# Filter_V0_2.net
KiCad netlist of a schematic drawn in EAGLE
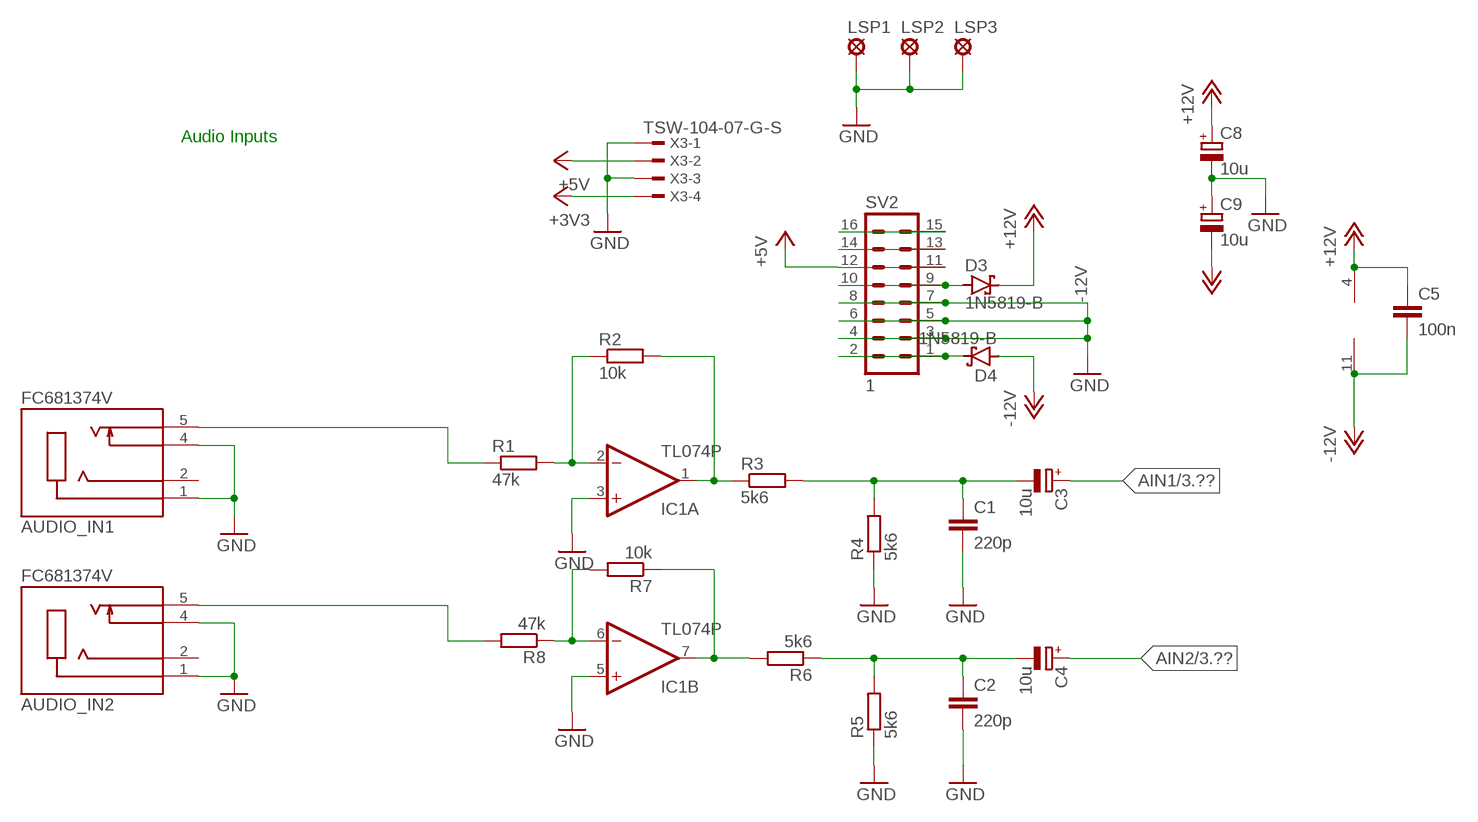
[diagram p0: schematic, sheet 1]
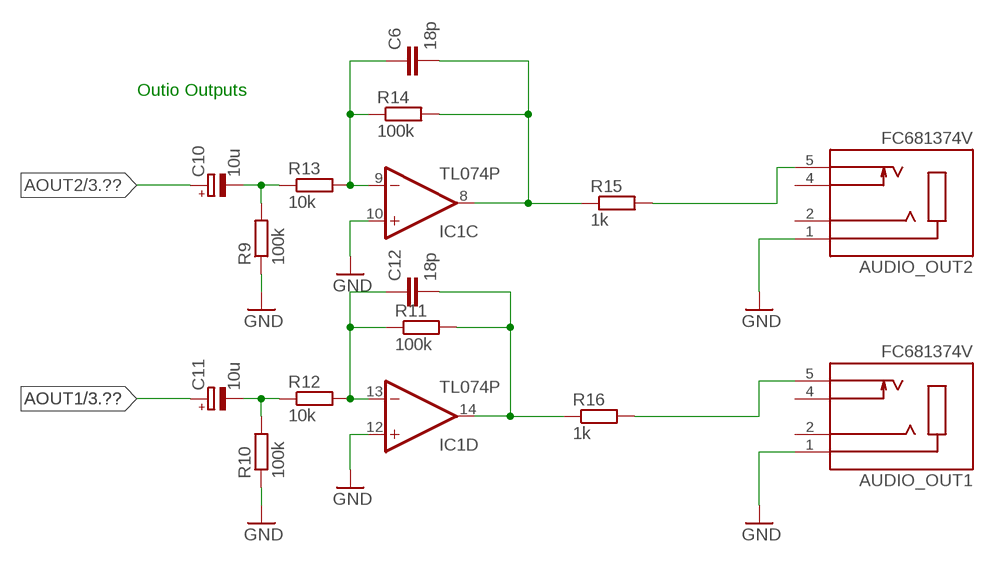
[diagram p1: schematic, sheet 2]
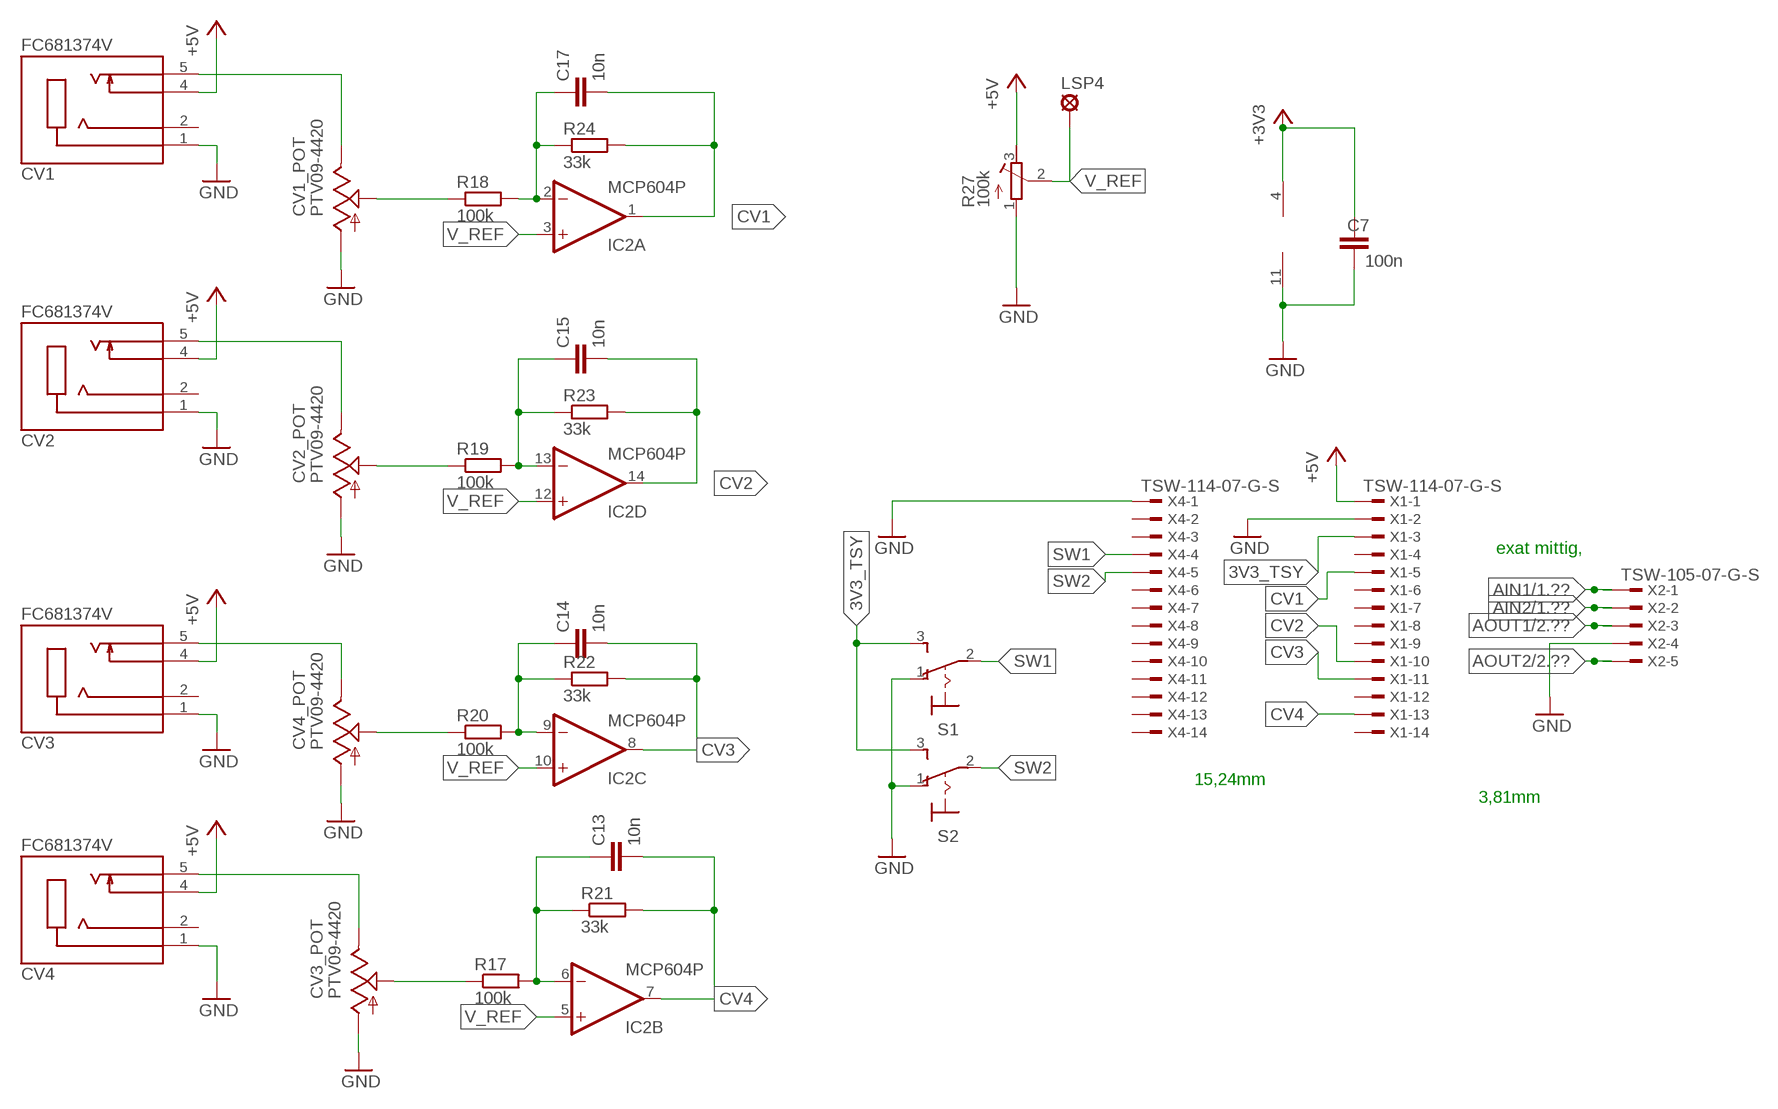
[diagram p2: schematic, sheet 3]

(export (version "E")
  (design (tool "Eeschema 10.0.6"))
  (components
    (comp (ref "C7")
      (value "100n")
      (footprint "eagle-import:C025-024X044")
      (libsource (lib "eagle-import") (part "C-EU025-024X044"))
    )
    (comp (ref "C13")
      (value "10n")
      (footprint "eagle-import:C025-024X044")
      (libsource (lib "eagle-import") (part "C-EU025-024X044"))
    )
    (comp (ref "C14")
      (value "10n")
      (footprint "eagle-import:C025-024X044")
      (libsource (lib "eagle-import") (part "C-EU025-024X044"))
    )
    (comp (ref "C15")
      (value "10n")
      (footprint "eagle-import:C025-024X044")
      (libsource (lib "eagle-import") (part "C-EU025-024X044"))
    )
    (comp (ref "C17")
      (value "10n")
      (footprint "eagle-import:C025-024X044")
      (libsource (lib "eagle-import") (part "C-EU025-024X044"))
    )
    (comp (ref "CV1")
      (value "FC681374V")
      (footprint "eagle-import:CLIFF_FC681374V")
      (fields (field (name "MF") "Cliff"))
      (libsource (lib "eagle-import") (part "FC681374V"))
    )
    (comp (ref "CV1_POT")
      (value "PTV09-4420")
      (footprint "eagle-import:PTV09")
      (fields (field (name "MF") "Nichifu") (field (name "MP") "PTV-09"))
      (libsource (lib "eagle-import") (part "PTV09-4420"))
    )
    (comp (ref "CV2")
      (value "FC681374V")
      (footprint "eagle-import:CLIFF_FC681374V")
      (fields (field (name "MF") "Cliff"))
      (libsource (lib "eagle-import") (part "FC681374V"))
    )
    (comp (ref "CV2_POT")
      (value "PTV09-4420")
      (footprint "eagle-import:PTV09")
      (fields (field (name "MF") "Nichifu") (field (name "MP") "PTV-09"))
      (libsource (lib "eagle-import") (part "PTV09-4420"))
    )
    (comp (ref "CV3")
      (value "FC681374V")
      (footprint "eagle-import:CLIFF_FC681374V")
      (fields (field (name "MF") "Cliff"))
      (libsource (lib "eagle-import") (part "FC681374V"))
    )
    (comp (ref "CV3_POT")
      (value "PTV09-4420")
      (footprint "eagle-import:PTV09")
      (fields (field (name "MF") "Nichifu") (field (name "MP") "PTV-09"))
      (libsource (lib "eagle-import") (part "PTV09-4420"))
    )
    (comp (ref "CV4")
      (value "FC681374V")
      (footprint "eagle-import:CLIFF_FC681374V")
      (fields (field (name "MF") "Cliff"))
      (libsource (lib "eagle-import") (part "FC681374V"))
    )
    (comp (ref "CV4_POT")
      (value "PTV09-4420")
      (footprint "eagle-import:PTV09")
      (fields (field (name "MF") "Nichifu") (field (name "MP") "PTV-09"))
      (libsource (lib "eagle-import") (part "PTV09-4420"))
    )
    (comp (ref "IC2")
      (value "MCP604P")
      (footprint "eagle-import:DIL14")
      (fields (field (name "SPICEPREFIX") "J"))
      (libsource (lib "eagle-import") (part "MCP604P"))
    )
    (comp (ref "LSP4")
      (value "LSP10")
      (footprint "eagle-import:LSP10")
      (libsource (lib "eagle-import") (part "LSP10"))
    )
    (comp (ref "R17")
      (value "100k")
      (footprint "eagle-import:0204_7")
      (libsource (lib "eagle-import") (part "R-EU_0204/7"))
    )
    (comp (ref "R18")
      (value "100k")
      (footprint "eagle-import:0204_7")
      (libsource (lib "eagle-import") (part "R-EU_0204/7"))
    )
    (comp (ref "R19")
      (value "100k")
      (footprint "eagle-import:0204_7")
      (libsource (lib "eagle-import") (part "R-EU_0204/7"))
    )
    (comp (ref "R20")
      (value "100k")
      (footprint "eagle-import:0204_7")
      (libsource (lib "eagle-import") (part "R-EU_0204/7"))
    )
    (comp (ref "R21")
      (value "33k")
      (footprint "eagle-import:0204_7")
      (libsource (lib "eagle-import") (part "R-EU_0204/7"))
    )
    (comp (ref "R22")
      (value "33k")
      (footprint "eagle-import:0204_7")
      (libsource (lib "eagle-import") (part "R-EU_0204/7"))
    )
    (comp (ref "R23")
      (value "33k")
      (footprint "eagle-import:0204_7")
      (libsource (lib "eagle-import") (part "R-EU_0204/7"))
    )
    (comp (ref "R24")
      (value "33k")
      (footprint "eagle-import:0204_7")
      (libsource (lib "eagle-import") (part "R-EU_0204/7"))
    )
    (comp (ref "R27")
      (value "100k")
      (footprint "eagle-import:RTRIM64W")
      (libsource (lib "eagle-import") (part "R-TRIMM64W"))
    )
    (comp (ref "S1")
      (value "M9040P")
      (footprint "eagle-import:M9040P")
      (libsource (lib "eagle-import") (part "M9040P"))
    )
    (comp (ref "S2")
      (value "M9040P")
      (footprint "eagle-import:M9040P")
      (libsource (lib "eagle-import") (part "M9040P"))
    )
    (comp (ref "X1")
      (value "TSW-114-07-G-S")
      (footprint "eagle-import:TSW-114-XX-G-S")
      (fields (field (name "MF") "Samtec Inc."))
      (libsource (lib "eagle-import") (part "TSW-114--G-S07"))
    )
    (comp (ref "X2")
      (value "TSW-105-07-G-S")
      (footprint "eagle-import:TSW-105-XX-G-S")
      (fields (field (name "MF") "Samtec Inc."))
      (libsource (lib "eagle-import") (part "TSW-105--G-S07"))
    )
    (comp (ref "X4")
      (value "TSW-114-07-G-S")
      (footprint "eagle-import:TSW-114-XX-G-S")
      (fields (field (name "MF") "Samtec Inc."))
      (libsource (lib "eagle-import") (part "TSW-114--G-S07"))
    )
    (comp (ref "AUDIO_IN1")
      (value "FC681374V")
      (footprint "eagle-import:CLIFF_FC681374V")
      (fields (field (name "MF") "Cliff"))
      (libsource (lib "eagle-import") (part "FC681374V"))
    )
    (comp (ref "AUDIO_IN2")
      (value "FC681374V")
      (footprint "eagle-import:CLIFF_FC681374V")
      (fields (field (name "MF") "Cliff"))
      (libsource (lib "eagle-import") (part "FC681374V"))
    )
    (comp (ref "C1")
      (value "220p")
      (footprint "eagle-import:C025-024X044")
      (libsource (lib "eagle-import") (part "C-EU025-024X044"))
    )
    (comp (ref "C2")
      (value "220p")
      (footprint "eagle-import:C025-024X044")
      (libsource (lib "eagle-import") (part "C-EU025-024X044"))
    )
    (comp (ref "C3")
      (value "10u")
      (footprint "eagle-import:E2,5-7")
      (libsource (lib "eagle-import") (part "CPOL-EUE2.5-7"))
    )
    (comp (ref "C4")
      (value "10u")
      (footprint "eagle-import:E2,5-7")
      (libsource (lib "eagle-import") (part "CPOL-EUE2.5-7"))
    )
    (comp (ref "C5")
      (value "100n")
      (footprint "eagle-import:C025-024X044")
      (libsource (lib "eagle-import") (part "C-EU025-024X044"))
    )
    (comp (ref "C8")
      (value "10u")
      (footprint "eagle-import:E2,5-7")
      (libsource (lib "eagle-import") (part "CPOL-EUE2.5-7"))
    )
    (comp (ref "C9")
      (value "10u")
      (footprint "eagle-import:E2,5-7")
      (libsource (lib "eagle-import") (part "CPOL-EUE2.5-7"))
    )
    (comp (ref "D3")
      (value "1N5819-B")
      (footprint "eagle-import:DO41-7.6")
      (libsource (lib "eagle-import") (part "1N5819-B"))
    )
    (comp (ref "D4")
      (value "1N5819-B")
      (footprint "eagle-import:DO41-7.6")
      (libsource (lib "eagle-import") (part "1N5819-B"))
    )
    (comp (ref "IC1")
      (value "TL074P")
      (footprint "eagle-import:DIL14")
      (libsource (lib "eagle-import") (part "TL074P"))
    )
    (comp (ref "LSP1")
      (value "LSP10")
      (footprint "eagle-import:LSP10")
      (libsource (lib "eagle-import") (part "LSP10"))
    )
    (comp (ref "LSP2")
      (value "LSP10")
      (footprint "eagle-import:LSP10")
      (libsource (lib "eagle-import") (part "LSP10"))
    )
    (comp (ref "LSP3")
      (value "LSP10")
      (footprint "eagle-import:LSP10")
      (libsource (lib "eagle-import") (part "LSP10"))
    )
    (comp (ref "R1")
      (value "47k")
      (footprint "eagle-import:0204_7")
      (libsource (lib "eagle-import") (part "R-EU_0204/7"))
    )
    (comp (ref "R2")
      (value "10k")
      (footprint "eagle-import:0204_7")
      (libsource (lib "eagle-import") (part "R-EU_0204/7"))
    )
    (comp (ref "R3")
      (value "5k6")
      (footprint "eagle-import:0204_7")
      (libsource (lib "eagle-import") (part "R-EU_0204/7"))
    )
    (comp (ref "R4")
      (value "5k6")
      (footprint "eagle-import:0204_7")
      (libsource (lib "eagle-import") (part "R-EU_0204/7"))
    )
    (comp (ref "R5")
      (value "5k6")
      (footprint "eagle-import:0204_7")
      (libsource (lib "eagle-import") (part "R-EU_0204/7"))
    )
    (comp (ref "R6")
      (value "5k6")
      (footprint "eagle-import:0204_7")
      (libsource (lib "eagle-import") (part "R-EU_0204/7"))
    )
    (comp (ref "R7")
      (value "10k")
      (footprint "eagle-import:0204_7")
      (libsource (lib "eagle-import") (part "R-EU_0204/7"))
    )
    (comp (ref "R8")
      (value "47k")
      (footprint "eagle-import:0204_7")
      (libsource (lib "eagle-import") (part "R-EU_0204/7"))
    )
    (comp (ref "SV2")
      (value "1")
      (footprint "eagle-import:ML16")
      (libsource (lib "eagle-import") (part "ML16"))
    )
    (comp (ref "X3")
      (value "TSW-104-07-G-S")
      (footprint "eagle-import:TSW-104-XX-G-S")
      (fields (field (name "MF") "Samtec Inc."))
      (libsource (lib "eagle-import") (part "TSW-104--G-S07"))
    )
    (comp (ref "AUDIO_OUT1")
      (value "FC681374V")
      (footprint "eagle-import:CLIFF_FC681374V")
      (fields (field (name "MF") "Cliff"))
      (libsource (lib "eagle-import") (part "FC681374V"))
    )
    (comp (ref "AUDIO_OUT2")
      (value "FC681374V")
      (footprint "eagle-import:CLIFF_FC681374V")
      (fields (field (name "MF") "Cliff"))
      (libsource (lib "eagle-import") (part "FC681374V"))
    )
    (comp (ref "C6")
      (value "18p")
      (footprint "eagle-import:C025-024X044")
      (libsource (lib "eagle-import") (part "C-EU025-024X044"))
    )
    (comp (ref "C10")
      (value "10u")
      (footprint "eagle-import:E2,5-7")
      (libsource (lib "eagle-import") (part "CPOL-EUE2.5-7"))
    )
    (comp (ref "C11")
      (value "10u")
      (footprint "eagle-import:E2,5-7")
      (libsource (lib "eagle-import") (part "CPOL-EUE2.5-7"))
    )
    (comp (ref "C12")
      (value "18p")
      (footprint "eagle-import:C025-024X044")
      (libsource (lib "eagle-import") (part "C-EU025-024X044"))
    )
    (comp (ref "R9")
      (value "100k")
      (footprint "eagle-import:0204_7")
      (libsource (lib "eagle-import") (part "R-EU_0204/7"))
    )
    (comp (ref "R10")
      (value "100k")
      (footprint "eagle-import:0204_7")
      (libsource (lib "eagle-import") (part "R-EU_0204/7"))
    )
    (comp (ref "R11")
      (value "100k")
      (footprint "eagle-import:0204_7")
      (libsource (lib "eagle-import") (part "R-EU_0204/7"))
    )
    (comp (ref "R12")
      (value "10k")
      (footprint "eagle-import:0204_7")
      (libsource (lib "eagle-import") (part "R-EU_0204/7"))
    )
    (comp (ref "R13")
      (value "10k")
      (footprint "eagle-import:0204_7")
      (libsource (lib "eagle-import") (part "R-EU_0204/7"))
    )
    (comp (ref "R14")
      (value "100k")
      (footprint "eagle-import:0204_7")
      (libsource (lib "eagle-import") (part "R-EU_0204/7"))
    )
    (comp (ref "R15")
      (value "1k")
      (footprint "eagle-import:0204_7")
      (libsource (lib "eagle-import") (part "R-EU_0204/7"))
    )
    (comp (ref "R16")
      (value "1k")
      (footprint "eagle-import:0204_7")
      (libsource (lib "eagle-import") (part "R-EU_0204/7"))
    )
  )
  (nets
    (net (code "1") (name "+3V3") (class "Default")
      (node (ref "C7") (pin "1") (pinfunction "1_1") (pintype "passive"))
      (node (ref "IC2") (pin "4") (pinfunction "V+_4") (pintype "power_in"))
      (node (ref "X3") (pin "4") (pinfunction "1_4") (pintype "passive"))
    )
    (net (code "2") (name "+5V") (class "Default")
      (node (ref "CV1") (pin "4") (pinfunction "4_4") (pintype "passive"))
      (node (ref "CV2") (pin "4") (pinfunction "4_4") (pintype "passive"))
      (node (ref "CV3") (pin "4") (pinfunction "4_4") (pintype "passive"))
      (node (ref "CV4") (pin "4") (pinfunction "4_4") (pintype "passive"))
      (node (ref "R27") (pin "3") (pinfunction "E_3") (pintype "passive"))
      (node (ref "SV2") (pin "11") (pinfunction "11_11") (pintype "passive"))
      (node (ref "SV2") (pin "12") (pinfunction "12_12") (pintype "passive"))
      (node (ref "X1") (pin "1") (pinfunction "1_1") (pintype "passive"))
      (node (ref "X3") (pin "2") (pinfunction "1_2") (pintype "passive"))
    )
    (net (code "3") (name "+12V") (class "Default")
      (node (ref "C5") (pin "1") (pinfunction "1_1") (pintype "passive"))
      (node (ref "C8") (pin "+") (pinfunction "+_+") (pintype "passive"))
      (node (ref "D3") (pin "C") (pinfunction "C_C") (pintype "passive"))
      (node (ref "IC1") (pin "4") (pinfunction "V+_4") (pintype "power_in"))
    )
    (net (code "4") (name "-12V") (class "Default")
      (node (ref "C5") (pin "2") (pinfunction "2_2") (pintype "passive"))
      (node (ref "C9") (pin "-") (pinfunction "-_-") (pintype "passive"))
      (node (ref "D4") (pin "A") (pinfunction "A_A") (pintype "passive"))
      (node (ref "IC1") (pin "11") (pinfunction "V-_11") (pintype "power_in"))
    )
    (net (code "5") (name "3V3_TSY") (class "Default")
      (node (ref "S1") (pin "3") (pinfunction "S_3") (pintype "passive"))
      (node (ref "S2") (pin "3") (pinfunction "S_3") (pintype "passive"))
      (node (ref "X1") (pin "3") (pinfunction "1_3") (pintype "passive"))
    )
    (net (code "6") (name "AIN1") (class "Default")
      (node (ref "C3") (pin "+") (pinfunction "+_+") (pintype "passive"))
      (node (ref "X2") (pin "1") (pinfunction "1_1") (pintype "passive"))
    )
    (net (code "7") (name "AIN2") (class "Default")
      (node (ref "C4") (pin "+") (pinfunction "+_+") (pintype "passive"))
      (node (ref "X2") (pin "2") (pinfunction "1_2") (pintype "passive"))
    )
    (net (code "8") (name "AOUT1") (class "Default")
      (node (ref "C11") (pin "+") (pinfunction "+_+") (pintype "passive"))
      (node (ref "X2") (pin "3") (pinfunction "1_3") (pintype "passive"))
    )
    (net (code "9") (name "AOUT2") (class "Default")
      (node (ref "C10") (pin "+") (pinfunction "+_+") (pintype "passive"))
      (node (ref "X2") (pin "5") (pinfunction "1_5") (pintype "passive"))
    )
    (net (code "10") (name "CV1") (class "Default")
      (node (ref "C17") (pin "2") (pinfunction "2_2") (pintype "passive"))
      (node (ref "IC2") (pin "1") (pinfunction "OUT_1") (pintype "output"))
      (node (ref "R24") (pin "2") (pinfunction "2_2") (pintype "passive"))
      (node (ref "X1") (pin "5") (pinfunction "1_5") (pintype "passive"))
    )
    (net (code "11") (name "CV2") (class "Default")
      (node (ref "C15") (pin "2") (pinfunction "2_2") (pintype "passive"))
      (node (ref "IC2") (pin "14") (pinfunction "OUT_14") (pintype "output"))
      (node (ref "R23") (pin "2") (pinfunction "2_2") (pintype "passive"))
      (node (ref "X1") (pin "10") (pinfunction "1_10") (pintype "passive"))
    )
    (net (code "12") (name "CV3") (class "Default")
      (node (ref "C14") (pin "2") (pinfunction "2_2") (pintype "passive"))
      (node (ref "IC2") (pin "8") (pinfunction "OUT_8") (pintype "output"))
      (node (ref "R22") (pin "2") (pinfunction "2_2") (pintype "passive"))
      (node (ref "X1") (pin "11") (pinfunction "1_11") (pintype "passive"))
    )
    (net (code "13") (name "CV4") (class "Default")
      (node (ref "C13") (pin "2") (pinfunction "2_2") (pintype "passive"))
      (node (ref "IC2") (pin "7") (pinfunction "OUT_7") (pintype "output"))
      (node (ref "R21") (pin "2") (pinfunction "2_2") (pintype "passive"))
      (node (ref "X1") (pin "13") (pinfunction "1_13") (pintype "passive"))
    )
    (net (code "14") (name "GND") (class "Default")
      (node (ref "AUDIO_IN1") (pin "1") (pinfunction "1_1") (pintype "passive"))
      (node (ref "AUDIO_IN1") (pin "4") (pinfunction "4_4") (pintype "passive"))
      (node (ref "AUDIO_IN2") (pin "1") (pinfunction "1_1") (pintype "passive"))
      (node (ref "AUDIO_IN2") (pin "4") (pinfunction "4_4") (pintype "passive"))
      (node (ref "AUDIO_OUT1") (pin "1") (pinfunction "1_1") (pintype "passive"))
      (node (ref "AUDIO_OUT2") (pin "1") (pinfunction "1_1") (pintype "passive"))
      (node (ref "C1") (pin "2") (pinfunction "2_2") (pintype "passive"))
      (node (ref "C2") (pin "2") (pinfunction "2_2") (pintype "passive"))
      (node (ref "C7") (pin "2") (pinfunction "2_2") (pintype "passive"))
      (node (ref "C8") (pin "-") (pinfunction "-_-") (pintype "passive"))
      (node (ref "C9") (pin "+") (pinfunction "+_+") (pintype "passive"))
      (node (ref "CV1") (pin "1") (pinfunction "1_1") (pintype "passive"))
      (node (ref "CV1_POT") (pin "1") (pinfunction "A_1") (pintype "passive"))
      (node (ref "CV2") (pin "1") (pinfunction "1_1") (pintype "passive"))
      (node (ref "CV2_POT") (pin "1") (pinfunction "A_1") (pintype "passive"))
      (node (ref "CV3") (pin "1") (pinfunction "1_1") (pintype "passive"))
      (node (ref "CV3_POT") (pin "1") (pinfunction "A_1") (pintype "passive"))
      (node (ref "CV4") (pin "1") (pinfunction "1_1") (pintype "passive"))
      (node (ref "CV4_POT") (pin "1") (pinfunction "A_1") (pintype "passive"))
      (node (ref "IC1") (pin "10") (pinfunction "+IN_10") (pintype "input"))
      (node (ref "IC1") (pin "12") (pinfunction "+IN_12") (pintype "input"))
      (node (ref "IC1") (pin "3") (pinfunction "+IN_3") (pintype "input"))
      (node (ref "IC1") (pin "5") (pinfunction "+IN_5") (pintype "input"))
      (node (ref "IC2") (pin "11") (pinfunction "V-_11") (pintype "power_in"))
      (node (ref "LSP1") (pin "MP") (pinfunction "MP_MP") (pintype "passive"))
      (node (ref "LSP2") (pin "MP") (pinfunction "MP_MP") (pintype "passive"))
      (node (ref "LSP3") (pin "MP") (pinfunction "MP_MP") (pintype "passive"))
      (node (ref "R10") (pin "1") (pinfunction "1_1") (pintype "passive"))
      (node (ref "R27") (pin "1") (pinfunction "A_1") (pintype "passive"))
      (node (ref "R4") (pin "1") (pinfunction "1_1") (pintype "passive"))
      (node (ref "R5") (pin "1") (pinfunction "1_1") (pintype "passive"))
      (node (ref "R9") (pin "1") (pinfunction "1_1") (pintype "passive"))
      (node (ref "S1") (pin "1") (pinfunction "O_1") (pintype "passive"))
      (node (ref "S2") (pin "1") (pinfunction "O_1") (pintype "passive"))
      (node (ref "SV2") (pin "3") (pinfunction "3_3") (pintype "passive"))
      (node (ref "SV2") (pin "4") (pinfunction "4_4") (pintype "passive"))
      (node (ref "SV2") (pin "5") (pinfunction "5_5") (pintype "passive"))
      (node (ref "SV2") (pin "6") (pinfunction "6_6") (pintype "passive"))
      (node (ref "SV2") (pin "7") (pinfunction "7_7") (pintype "passive"))
      (node (ref "SV2") (pin "8") (pinfunction "8_8") (pintype "passive"))
      (node (ref "X1") (pin "2") (pinfunction "1_2") (pintype "passive"))
      (node (ref "X2") (pin "4") (pinfunction "1_4") (pintype "passive"))
      (node (ref "X3") (pin "1") (pinfunction "1_1") (pintype "passive"))
      (node (ref "X3") (pin "3") (pinfunction "1_3") (pintype "passive"))
      (node (ref "X4") (pin "1") (pinfunction "1_1") (pintype "passive"))
    )
    (net (code "15") (name "Net-(AUDIO_IN1-Pad5)") (class "Default")
      (node (ref "AUDIO_IN1") (pin "5") (pinfunction "5_5") (pintype "passive"))
      (node (ref "R1") (pin "1") (pinfunction "1_1") (pintype "passive"))
    )
    (net (code "16") (name "Net-(AUDIO_IN2-Pad5)") (class "Default")
      (node (ref "AUDIO_IN2") (pin "5") (pinfunction "5_5") (pintype "passive"))
      (node (ref "R8") (pin "2") (pinfunction "2_2") (pintype "passive"))
    )
    (net (code "17") (name "Net-(AUDIO_OUT1-Pad5)") (class "Default")
      (node (ref "AUDIO_OUT1") (pin "5") (pinfunction "5_5") (pintype "passive"))
      (node (ref "R16") (pin "2") (pinfunction "2_2") (pintype "passive"))
    )
    (net (code "18") (name "Net-(AUDIO_OUT2-Pad5)") (class "Default")
      (node (ref "AUDIO_OUT2") (pin "5") (pinfunction "5_5") (pintype "passive"))
      (node (ref "R15") (pin "2") (pinfunction "2_2") (pintype "passive"))
    )
    (net (code "19") (name "Net-(C1-Pad1)") (class "Default")
      (node (ref "C1") (pin "1") (pinfunction "1_1") (pintype "passive"))
      (node (ref "C3") (pin "-") (pinfunction "-_-") (pintype "passive"))
      (node (ref "R3") (pin "2") (pinfunction "2_2") (pintype "passive"))
      (node (ref "R4") (pin "2") (pinfunction "2_2") (pintype "passive"))
    )
    (net (code "20") (name "Net-(C2-Pad1)") (class "Default")
      (node (ref "C2") (pin "1") (pinfunction "1_1") (pintype "passive"))
      (node (ref "C4") (pin "-") (pinfunction "-_-") (pintype "passive"))
      (node (ref "R5") (pin "2") (pinfunction "2_2") (pintype "passive"))
      (node (ref "R6") (pin "1") (pinfunction "1_1") (pintype "passive"))
    )
    (net (code "21") (name "Net-(C10-Pad-)") (class "Default")
      (node (ref "C10") (pin "-") (pinfunction "-_-") (pintype "passive"))
      (node (ref "R13") (pin "1") (pinfunction "1_1") (pintype "passive"))
      (node (ref "R9") (pin "2") (pinfunction "2_2") (pintype "passive"))
    )
    (net (code "22") (name "Net-(C11-Pad-)") (class "Default")
      (node (ref "C11") (pin "-") (pinfunction "-_-") (pintype "passive"))
      (node (ref "R10") (pin "2") (pinfunction "2_2") (pintype "passive"))
      (node (ref "R12") (pin "1") (pinfunction "1_1") (pintype "passive"))
    )
    (net (code "23") (name "Net-(CV1_POT-E)") (class "Default")
      (node (ref "CV1") (pin "5") (pinfunction "5_5") (pintype "passive"))
      (node (ref "CV1_POT") (pin "3") (pinfunction "E_3") (pintype "passive"))
    )
    (net (code "24") (name "Net-(CV1_POT-S)") (class "Default")
      (node (ref "CV1_POT") (pin "2") (pinfunction "S_2") (pintype "passive"))
      (node (ref "R18") (pin "1") (pinfunction "1_1") (pintype "passive"))
    )
    (net (code "25") (name "Net-(CV2_POT-E)") (class "Default")
      (node (ref "CV2") (pin "5") (pinfunction "5_5") (pintype "passive"))
      (node (ref "CV2_POT") (pin "3") (pinfunction "E_3") (pintype "passive"))
    )
    (net (code "26") (name "Net-(CV2_POT-S)") (class "Default")
      (node (ref "CV2_POT") (pin "2") (pinfunction "S_2") (pintype "passive"))
      (node (ref "R19") (pin "1") (pinfunction "1_1") (pintype "passive"))
    )
    (net (code "27") (name "Net-(CV3_POT-E)") (class "Default")
      (node (ref "CV3_POT") (pin "3") (pinfunction "E_3") (pintype "passive"))
      (node (ref "CV4") (pin "5") (pinfunction "5_5") (pintype "passive"))
    )
    (net (code "28") (name "Net-(CV3_POT-S)") (class "Default")
      (node (ref "CV3_POT") (pin "2") (pinfunction "S_2") (pintype "passive"))
      (node (ref "R17") (pin "1") (pinfunction "1_1") (pintype "passive"))
    )
    (net (code "29") (name "Net-(CV4_POT-E)") (class "Default")
      (node (ref "CV3") (pin "5") (pinfunction "5_5") (pintype "passive"))
      (node (ref "CV4_POT") (pin "3") (pinfunction "E_3") (pintype "passive"))
    )
    (net (code "30") (name "Net-(CV4_POT-S)") (class "Default")
      (node (ref "CV4_POT") (pin "2") (pinfunction "S_2") (pintype "passive"))
      (node (ref "R20") (pin "1") (pinfunction "1_1") (pintype "passive"))
    )
    (net (code "31") (name "Net-(D3-PadA)") (class "Default")
      (node (ref "D3") (pin "A") (pinfunction "A_A") (pintype "passive"))
      (node (ref "SV2") (pin "10") (pinfunction "10_10") (pintype "passive"))
      (node (ref "SV2") (pin "9") (pinfunction "9_9") (pintype "passive"))
    )
    (net (code "32") (name "Net-(D4-PadC)") (class "Default")
      (node (ref "D4") (pin "C") (pinfunction "C_C") (pintype "passive"))
      (node (ref "SV2") (pin "1") (pinfunction "1_1") (pintype "passive"))
      (node (ref "SV2") (pin "2") (pinfunction "2_2") (pintype "passive"))
    )
    (net (code "33") (name "Net-(IC1A--IN)") (class "Default")
      (node (ref "IC1") (pin "2") (pinfunction "-IN_2") (pintype "input"))
      (node (ref "R1") (pin "2") (pinfunction "2_2") (pintype "passive"))
      (node (ref "R2") (pin "1") (pinfunction "1_1") (pintype "passive"))
    )
    (net (code "34") (name "Net-(IC1A-OUT)") (class "Default")
      (node (ref "IC1") (pin "1") (pinfunction "OUT_1") (pintype "output"))
      (node (ref "R2") (pin "2") (pinfunction "2_2") (pintype "passive"))
      (node (ref "R3") (pin "1") (pinfunction "1_1") (pintype "passive"))
    )
    (net (code "35") (name "Net-(IC1B--IN)") (class "Default")
      (node (ref "IC1") (pin "6") (pinfunction "-IN_6") (pintype "input"))
      (node (ref "R7") (pin "2") (pinfunction "2_2") (pintype "passive"))
      (node (ref "R8") (pin "1") (pinfunction "1_1") (pintype "passive"))
    )
    (net (code "36") (name "Net-(IC1B-OUT)") (class "Default")
      (node (ref "IC1") (pin "7") (pinfunction "OUT_7") (pintype "output"))
      (node (ref "R6") (pin "2") (pinfunction "2_2") (pintype "passive"))
      (node (ref "R7") (pin "1") (pinfunction "1_1") (pintype "passive"))
    )
    (net (code "37") (name "Net-(IC1C--IN)") (class "Default")
      (node (ref "C6") (pin "1") (pinfunction "1_1") (pintype "passive"))
      (node (ref "IC1") (pin "9") (pinfunction "-IN_9") (pintype "input"))
      (node (ref "R13") (pin "2") (pinfunction "2_2") (pintype "passive"))
      (node (ref "R14") (pin "1") (pinfunction "1_1") (pintype "passive"))
    )
    (net (code "38") (name "Net-(IC1C-OUT)") (class "Default")
      (node (ref "C6") (pin "2") (pinfunction "2_2") (pintype "passive"))
      (node (ref "IC1") (pin "8") (pinfunction "OUT_8") (pintype "output"))
      (node (ref "R14") (pin "2") (pinfunction "2_2") (pintype "passive"))
      (node (ref "R15") (pin "1") (pinfunction "1_1") (pintype "passive"))
    )
    (net (code "39") (name "Net-(IC1D--IN)") (class "Default")
      (node (ref "C12") (pin "1") (pinfunction "1_1") (pintype "passive"))
      (node (ref "IC1") (pin "13") (pinfunction "-IN_13") (pintype "input"))
      (node (ref "R11") (pin "1") (pinfunction "1_1") (pintype "passive"))
      (node (ref "R12") (pin "2") (pinfunction "2_2") (pintype "passive"))
    )
    (net (code "40") (name "Net-(IC1D-OUT)") (class "Default")
      (node (ref "C12") (pin "2") (pinfunction "2_2") (pintype "passive"))
      (node (ref "IC1") (pin "14") (pinfunction "OUT_14") (pintype "output"))
      (node (ref "R11") (pin "2") (pinfunction "2_2") (pintype "passive"))
      (node (ref "R16") (pin "1") (pinfunction "1_1") (pintype "passive"))
    )
    (net (code "41") (name "Net-(IC2A--IN)") (class "Default")
      (node (ref "C17") (pin "1") (pinfunction "1_1") (pintype "passive"))
      (node (ref "IC2") (pin "2") (pinfunction "-IN_2") (pintype "input"))
      (node (ref "R18") (pin "2") (pinfunction "2_2") (pintype "passive"))
      (node (ref "R24") (pin "1") (pinfunction "1_1") (pintype "passive"))
    )
    (net (code "42") (name "Net-(IC2B--IN)") (class "Default")
      (node (ref "C13") (pin "1") (pinfunction "1_1") (pintype "passive"))
      (node (ref "IC2") (pin "6") (pinfunction "-IN_6") (pintype "input"))
      (node (ref "R17") (pin "2") (pinfunction "2_2") (pintype "passive"))
      (node (ref "R21") (pin "1") (pinfunction "1_1") (pintype "passive"))
    )
    (net (code "43") (name "Net-(IC2C--IN)") (class "Default")
      (node (ref "C14") (pin "1") (pinfunction "1_1") (pintype "passive"))
      (node (ref "IC2") (pin "9") (pinfunction "-IN_9") (pintype "input"))
      (node (ref "R20") (pin "2") (pinfunction "2_2") (pintype "passive"))
      (node (ref "R22") (pin "1") (pinfunction "1_1") (pintype "passive"))
    )
    (net (code "44") (name "Net-(IC2D--IN)") (class "Default")
      (node (ref "C15") (pin "1") (pinfunction "1_1") (pintype "passive"))
      (node (ref "IC2") (pin "13") (pinfunction "-IN_13") (pintype "input"))
      (node (ref "R19") (pin "2") (pinfunction "2_2") (pintype "passive"))
      (node (ref "R23") (pin "1") (pinfunction "1_1") (pintype "passive"))
    )
    (net (code "45") (name "Net-(SV2-Pad13)") (class "Default")
      (node (ref "SV2") (pin "13") (pinfunction "13_13") (pintype "passive"))
      (node (ref "SV2") (pin "14") (pinfunction "14_14") (pintype "passive"))
    )
    (net (code "46") (name "Net-(SV2-Pad15)") (class "Default")
      (node (ref "SV2") (pin "15") (pinfunction "15_15") (pintype "passive"))
      (node (ref "SV2") (pin "16") (pinfunction "16_16") (pintype "passive"))
    )
    (net (code "47") (name "SW1") (class "Default")
      (node (ref "S1") (pin "2") (pinfunction "P_2") (pintype "passive"))
      (node (ref "X4") (pin "4") (pinfunction "1_4") (pintype "passive"))
    )
    (net (code "48") (name "SW2") (class "Default")
      (node (ref "S2") (pin "2") (pinfunction "P_2") (pintype "passive"))
      (node (ref "X4") (pin "5") (pinfunction "1_5") (pintype "passive"))
    )
    (net (code "49") (name "V_REF") (class "Default")
      (node (ref "IC2") (pin "10") (pinfunction "+IN_10") (pintype "input"))
      (node (ref "IC2") (pin "12") (pinfunction "+IN_12") (pintype "input"))
      (node (ref "IC2") (pin "3") (pinfunction "+IN_3") (pintype "input"))
      (node (ref "IC2") (pin "5") (pinfunction "+IN_5") (pintype "input"))
      (node (ref "LSP4") (pin "MP") (pinfunction "MP_MP") (pintype "passive"))
      (node (ref "R27") (pin "2") (pinfunction "S_2") (pintype "passive"))
    )
    (net (code "50") (name "unconnected-(AUDIO_IN1-Pad2)") (class "Default")
      (node (ref "AUDIO_IN1") (pin "2") (pinfunction "2_2") (pintype "passive"))
    )
    (net (code "51") (name "unconnected-(AUDIO_IN2-Pad2)") (class "Default")
      (node (ref "AUDIO_IN2") (pin "2") (pinfunction "2_2") (pintype "passive"))
    )
    (net (code "52") (name "unconnected-(AUDIO_OUT1-Pad2)") (class "Default")
      (node (ref "AUDIO_OUT1") (pin "2") (pinfunction "2_2") (pintype "passive"))
    )
    (net (code "53") (name "unconnected-(AUDIO_OUT1-Pad4)") (class "Default")
      (node (ref "AUDIO_OUT1") (pin "4") (pinfunction "4_4") (pintype "passive"))
    )
    (net (code "54") (name "unconnected-(AUDIO_OUT2-Pad2)") (class "Default")
      (node (ref "AUDIO_OUT2") (pin "2") (pinfunction "2_2") (pintype "passive"))
    )
    (net (code "55") (name "unconnected-(AUDIO_OUT2-Pad4)") (class "Default")
      (node (ref "AUDIO_OUT2") (pin "4") (pinfunction "4_4") (pintype "passive"))
    )
    (net (code "56") (name "unconnected-(CV1-Pad2)") (class "Default")
      (node (ref "CV1") (pin "2") (pinfunction "2_2") (pintype "passive"))
    )
    (net (code "57") (name "unconnected-(CV2-Pad2)") (class "Default")
      (node (ref "CV2") (pin "2") (pinfunction "2_2") (pintype "passive"))
    )
    (net (code "58") (name "unconnected-(CV3-Pad2)") (class "Default")
      (node (ref "CV3") (pin "2") (pinfunction "2_2") (pintype "passive"))
    )
    (net (code "59") (name "unconnected-(CV4-Pad2)") (class "Default")
      (node (ref "CV4") (pin "2") (pinfunction "2_2") (pintype "passive"))
    )
    (net (code "60") (name "unconnected-(X1D-1-Pad12)") (class "Default")
      (node (ref "X1") (pin "12") (pinfunction "1_12") (pintype "passive"))
    )
    (net (code "61") (name "unconnected-(X1F-1-Pad14)") (class "Default")
      (node (ref "X1") (pin "14") (pinfunction "1_14") (pintype "passive"))
    )
    (net (code "62") (name "unconnected-(X1I-1-Pad4)") (class "Default")
      (node (ref "X1") (pin "4") (pinfunction "1_4") (pintype "passive"))
    )
    (net (code "63") (name "unconnected-(X1K-1-Pad6)") (class "Default")
      (node (ref "X1") (pin "6") (pinfunction "1_6") (pintype "passive"))
    )
    (net (code "64") (name "unconnected-(X1L-1-Pad7)") (class "Default")
      (node (ref "X1") (pin "7") (pinfunction "1_7") (pintype "passive"))
    )
    (net (code "65") (name "unconnected-(X1M-1-Pad8)") (class "Default")
      (node (ref "X1") (pin "8") (pinfunction "1_8") (pintype "passive"))
    )
    (net (code "66") (name "unconnected-(X1N-1-Pad9)") (class "Default")
      (node (ref "X1") (pin "9") (pinfunction "1_9") (pintype "passive"))
    )
    (net (code "67") (name "unconnected-(X4B-1-Pad10)") (class "Default")
      (node (ref "X4") (pin "10") (pinfunction "1_10") (pintype "passive"))
    )
    (net (code "68") (name "unconnected-(X4C-1-Pad11)") (class "Default")
      (node (ref "X4") (pin "11") (pinfunction "1_11") (pintype "passive"))
    )
    (net (code "69") (name "unconnected-(X4D-1-Pad12)") (class "Default")
      (node (ref "X4") (pin "12") (pinfunction "1_12") (pintype "passive"))
    )
    (net (code "70") (name "unconnected-(X4E-1-Pad13)") (class "Default")
      (node (ref "X4") (pin "13") (pinfunction "1_13") (pintype "passive"))
    )
    (net (code "71") (name "unconnected-(X4F-1-Pad14)") (class "Default")
      (node (ref "X4") (pin "14") (pinfunction "1_14") (pintype "passive"))
    )
    (net (code "72") (name "unconnected-(X4G-1-Pad2)") (class "Default")
      (node (ref "X4") (pin "2") (pinfunction "1_2") (pintype "passive"))
    )
    (net (code "73") (name "unconnected-(X4H-1-Pad3)") (class "Default")
      (node (ref "X4") (pin "3") (pinfunction "1_3") (pintype "passive"))
    )
    (net (code "74") (name "unconnected-(X4K-1-Pad6)") (class "Default")
      (node (ref "X4") (pin "6") (pinfunction "1_6") (pintype "passive"))
    )
    (net (code "75") (name "unconnected-(X4L-1-Pad7)") (class "Default")
      (node (ref "X4") (pin "7") (pinfunction "1_7") (pintype "passive"))
    )
    (net (code "76") (name "unconnected-(X4M-1-Pad8)") (class "Default")
      (node (ref "X4") (pin "8") (pinfunction "1_8") (pintype "passive"))
    )
    (net (code "77") (name "unconnected-(X4N-1-Pad9)") (class "Default")
      (node (ref "X4") (pin "9") (pinfunction "1_9") (pintype "passive"))
    )
  )
)
